# 05_RS232_USB.net
KiCad netlist of a schematic drawn in Altium Designer
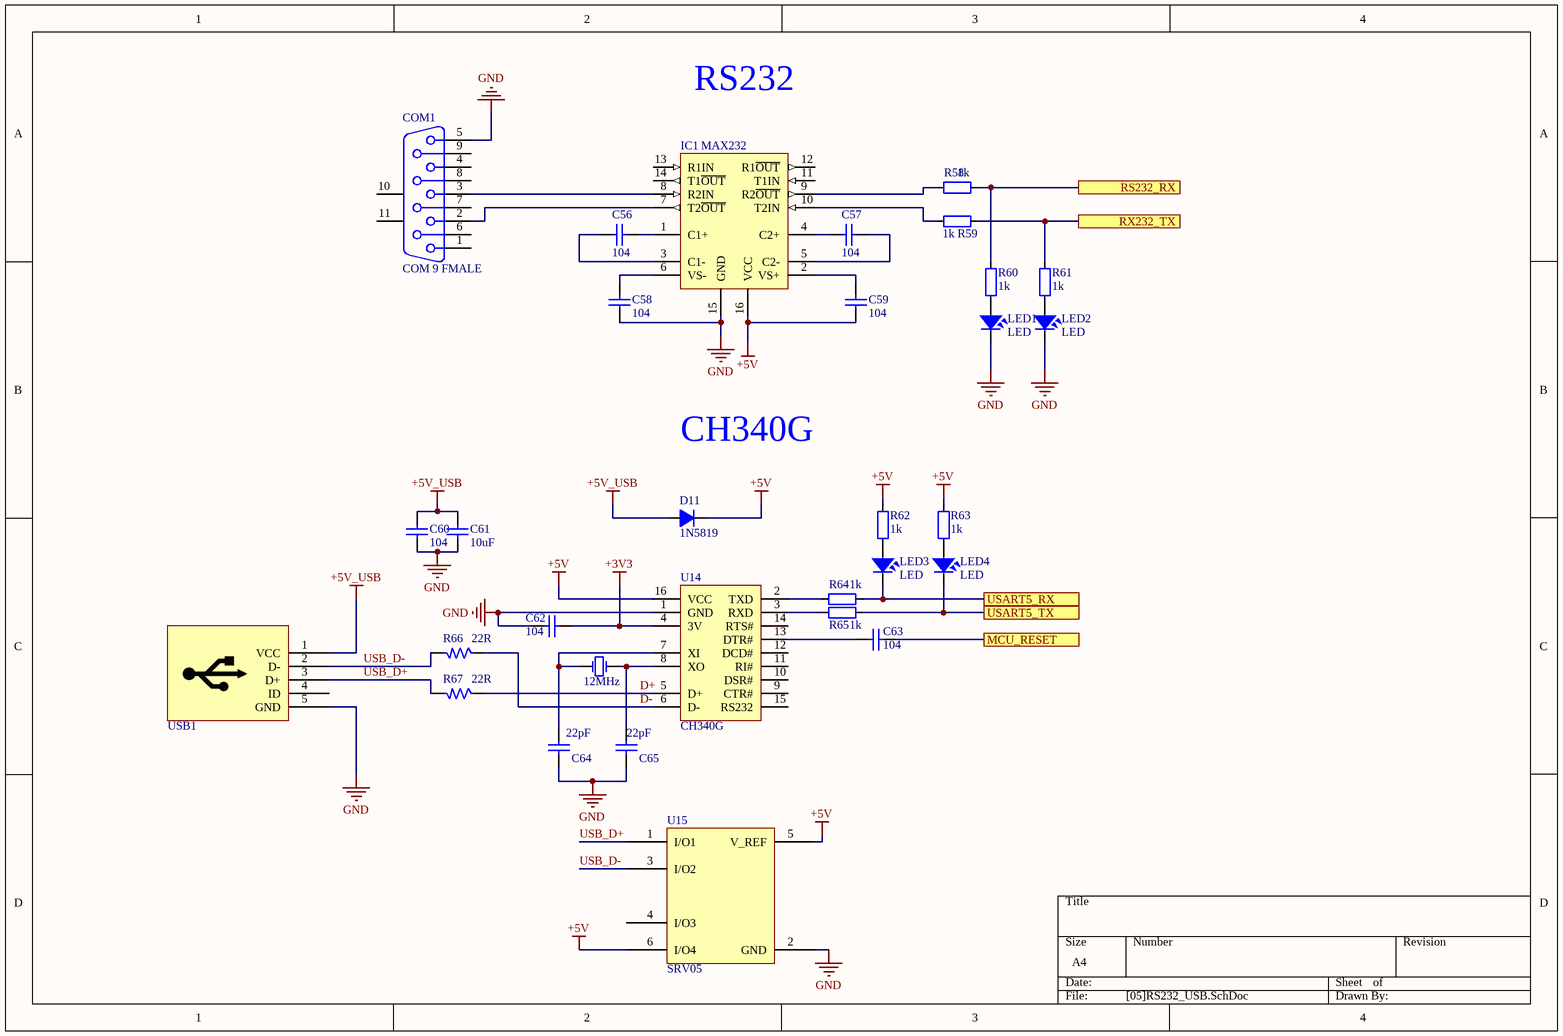
[diagram p0: [05]RS232_USB.SchDoc]

(export (version "E")
  (design (tool "Eeschema 10.0.6"))
  (components
    (comp (ref "C56")
      (value "104")
      (footprint "CAP_0603")
      (description "Capacitor")
      (fields (field (name "PUBLISHER") "Altium Limited"))
      (libsource (lib "My Library") (part "CapSMD"))
    )
    (comp (ref "C57")
      (value "104")
      (footprint "CAP_0603")
      (description "Capacitor")
      (fields (field (name "PUBLISHER") "Altium Limited"))
      (libsource (lib "My Library") (part "CapSMD"))
    )
    (comp (ref "C58")
      (value "104")
      (footprint "CAP_0603")
      (description "Capacitor")
      (fields (field (name "PUBLISHER") "Altium Limited"))
      (libsource (lib "My Library") (part "CapSMD"))
    )
    (comp (ref "C59")
      (value "104")
      (footprint "CAP_0603")
      (description "Capacitor")
      (fields (field (name "PUBLISHER") "Altium Limited"))
      (libsource (lib "My Library") (part "CapSMD"))
    )
    (comp (ref "C60")
      (value "104")
      (footprint "CAP_0603")
      (description "Capacitor")
      (fields (field (name "PUBLISHER") "Altium Limited"))
      (libsource (lib "My Library") (part "CapSMD"))
    )
    (comp (ref "C61")
      (value "10uF")
      (footprint "CAP_0603")
      (description "Capacitor")
      (fields (field (name "PUBLISHER") "Altium Limited"))
      (libsource (lib "My Library") (part "CapSMD"))
    )
    (comp (ref "C62")
      (value "104")
      (footprint "CAP_0603")
      (description "Capacitor")
      (fields (field (name "PUBLISHER") "Altium Limited"))
      (libsource (lib "My Library") (part "CapSMD"))
    )
    (comp (ref "C63")
      (value "104")
      (footprint "CAP_0603")
      (description "Capacitor")
      (fields (field (name "PUBLISHER") "Altium Limited"))
      (libsource (lib "My Library") (part "CapSMD"))
    )
    (comp (ref "C64")
      (value "22pF")
      (footprint "CAP_0603")
      (description "Capacitor")
      (fields (field (name "PUBLISHER") "Altium Limited"))
      (libsource (lib "My Library") (part "CapSMD"))
    )
    (comp (ref "C65")
      (value "22pF")
      (footprint "CAP_0603")
      (description "Capacitor")
      (fields (field (name "PUBLISHER") "Altium Limited"))
      (libsource (lib "My Library") (part "CapSMD"))
    )
    (comp (ref "COM1")
      (value "COM 9 FMALE")
      (footprint "DSB 9-F")
      (description "COM 9")
      (fields (field (name "PUBLISHER") "Altium Limited"))
      (libsource (lib "syhaunguyen") (part "DSB9F"))
    )
    (comp (ref "D11")
      (value "1N5819")
      (footprint "DO-214AB SMA")
      (description "Diode 1A")
      (libsource (lib "GPS_Traking_V1_1") (part "D1A_1"))
    )
    (comp (ref "IC1")
      (value "MAX232")
      (footprint "MAX232DR")
      (description "Dual EIA-232 Driver/Receiver")
      (libsource (lib "My Library") (part "MAX232"))
    )
    (comp (ref "LED1")
      (value "LED")
      (footprint "LED-0805-Green")
      (description "LED Single colour Green and Red")
      (libsource (lib "My Library") (part "LED"))
    )
    (comp (ref "LED2")
      (value "LED")
      (footprint "LED-0805-Green")
      (description "LED Single colour Green and Red")
      (libsource (lib "My Library") (part "LED"))
    )
    (comp (ref "LED3")
      (value "LED")
      (footprint "LED-0805-Green")
      (description "LED Single colour Green and Red")
      (libsource (lib "My Library") (part "LED"))
    )
    (comp (ref "LED4")
      (value "LED")
      (footprint "LED-0805-Green")
      (description "LED Single colour Green and Red")
      (libsource (lib "My Library") (part "LED"))
    )
    (comp (ref "R58")
      (value "1k")
      (footprint "RES-SMD-0603")
      (description "Resistor")
      (fields
        (field (name "MANUFACTURER") "Generic Components")
        (field (name "PUBLISHER") "Altium Hobart Technology Centre")
      )
      (libsource (lib "My Library") (part "Resistor - SMD"))
    )
    (comp (ref "R59")
      (value "1k")
      (footprint "RES-SMD-0603")
      (description "Resistor")
      (fields
        (field (name "MANUFACTURER") "Generic Components")
        (field (name "PUBLISHER") "Altium Hobart Technology Centre")
      )
      (libsource (lib "My Library") (part "Resistor - SMD"))
    )
    (comp (ref "R60")
      (value "1k")
      (footprint "RES-SMD-0603")
      (description "Resistor")
      (fields
        (field (name "MANUFACTURER") "Generic Components")
        (field (name "PUBLISHER") "Altium Hobart Technology Centre")
      )
      (libsource (lib "My Library") (part "Resistor - SMD"))
    )
    (comp (ref "R61")
      (value "1k")
      (footprint "RES-SMD-0603")
      (description "Resistor")
      (fields
        (field (name "MANUFACTURER") "Generic Components")
        (field (name "PUBLISHER") "Altium Hobart Technology Centre")
      )
      (libsource (lib "My Library") (part "Resistor - SMD"))
    )
    (comp (ref "R62")
      (value "1k")
      (footprint "RES-SMD-0603")
      (description "Resistor")
      (fields
        (field (name "MANUFACTURER") "Generic Components")
        (field (name "PUBLISHER") "Altium Hobart Technology Centre")
      )
      (libsource (lib "My Library") (part "Resistor - SMD"))
    )
    (comp (ref "R63")
      (value "1k")
      (footprint "RES-SMD-0603")
      (description "Resistor")
      (fields
        (field (name "MANUFACTURER") "Generic Components")
        (field (name "PUBLISHER") "Altium Hobart Technology Centre")
      )
      (libsource (lib "My Library") (part "Resistor - SMD"))
    )
    (comp (ref "R64")
      (value "1k")
      (footprint "RES-SMD-0603")
      (description "Resistor")
      (fields
        (field (name "MANUFACTURER") "Generic Components")
        (field (name "PUBLISHER") "Altium Hobart Technology Centre")
      )
      (libsource (lib "My Library") (part "Resistor - SMD"))
    )
    (comp (ref "R65")
      (value "1k")
      (footprint "RES-SMD-0603")
      (description "Resistor")
      (fields
        (field (name "MANUFACTURER") "Generic Components")
        (field (name "PUBLISHER") "Altium Hobart Technology Centre")
      )
      (libsource (lib "My Library") (part "Resistor - SMD"))
    )
    (comp (ref "R66")
      (value "22R")
      (footprint "RES-SMD-0603")
      (description "Resistor SMD")
      (libsource (lib "GPS_Traking_V1_1") (part "RM"))
    )
    (comp (ref "R67")
      (value "22R")
      (footprint "RES-SMD-0603")
      (description "Resistor SMD")
      (libsource (lib "GPS_Traking_V1_1") (part "RM"))
    )
    (comp (ref "U14")
      (value "CH340G")
      (footprint "SO16")
      (description "High and Low Side Driver")
      (fields (field (name "PUBLISHER") "Altium Limited"))
      (libsource (lib "My Library") (part "CH340G"))
    )
    (comp (ref "U15")
      (value "SRV05")
      (footprint "SOT23-6")
      (description "TVS DIODE 5V")
      (libsource (lib "My Library") (part "SRV05"))
    )
    (comp (ref "USB1") (value "USB") (footprint "USB-B-Mini") (libsource (lib "My Library") (part "USB-M")))
    (comp (ref "Y2")
      (value "12MHz")
      (footprint "XTAL-5032")
      (description "Crystal Oscillator")
      (fields (field (name "PUBLISHER") "Altium Limited"))
      (libsource (lib "My Library") (part "XTAL"))
    )
  )
  (nets
    (net (code "1") (name "+3V3") (class "Default")
      (node (ref "C62") (pin "2") (pinfunction "2_2") (pintype "passive"))
      (node (ref "U14") (pin "4") (pinfunction "3V_4") (pintype "passive"))
    )
    (net (code "2") (name "+5V") (class "Default")
      (node (ref "C59") (pin "2") (pinfunction "2_2") (pintype "passive"))
      (node (ref "D11") (pin "2") (pinfunction "K_2") (pintype "passive"))
      (node (ref "IC1") (pin "16") (pinfunction "VCC_16") (pintype "power_in"))
      (node (ref "R62") (pin "2") (pinfunction "2_2") (pintype "passive"))
      (node (ref "R63") (pin "2") (pinfunction "2_2") (pintype "passive"))
      (node (ref "U14") (pin "16") (pinfunction "VCC_16") (pintype "passive"))
      (node (ref "U15") (pin "5") (pinfunction "V_REF_5") (pintype "passive"))
      (node (ref "U15") (pin "6") (pinfunction "I/O4_6") (pintype "passive"))
    )
    (net (code "3") (name "+5V_USB") (class "Default")
      (node (ref "C60") (pin "2") (pinfunction "2_2") (pintype "passive"))
      (node (ref "C61") (pin "2") (pinfunction "2_2") (pintype "passive"))
      (node (ref "D11") (pin "1") (pinfunction "A_1") (pintype "passive"))
      (node (ref "USB1") (pin "1") (pinfunction "VCC_1") (pintype "passive"))
    )
    (net (code "4") (name "/D+") (class "Default")
      (node (ref "R67") (pin "1") (pinfunction "1_1") (pintype "passive"))
      (node (ref "U14") (pin "5") (pinfunction "D+_5") (pintype "passive"))
    )
    (net (code "5") (name "/D-") (class "Default")
      (node (ref "R66") (pin "1") (pinfunction "1_1") (pintype "passive"))
      (node (ref "U14") (pin "6") (pinfunction "D-_6") (pintype "passive"))
    )
    (net (code "6") (name "/MCU_RESET") (class "Default")
      (node (ref "C63") (pin "2") (pinfunction "2_2") (pintype "passive"))
    )
    (net (code "7") (name "/RS232_RX") (class "Default")
      (node (ref "R58") (pin "1") (pinfunction "1_1") (pintype "passive"))
      (node (ref "R60") (pin "2") (pinfunction "2_2") (pintype "passive"))
    )
    (net (code "8") (name "/RX232_TX") (class "Default")
      (node (ref "R59") (pin "1") (pinfunction "1_1") (pintype "passive"))
      (node (ref "R61") (pin "2") (pinfunction "2_2") (pintype "passive"))
    )
    (net (code "9") (name "/USART5_RX") (class "Default")
      (node (ref "LED3") (pin "2") (pinfunction "2_2") (pintype "passive"))
      (node (ref "R64") (pin "2") (pinfunction "2_2") (pintype "passive"))
    )
    (net (code "10") (name "/USART5_TX") (class "Default")
      (node (ref "LED4") (pin "2") (pinfunction "2_2") (pintype "passive"))
      (node (ref "R65") (pin "2") (pinfunction "2_2") (pintype "passive"))
    )
    (net (code "11") (name "/USB_D+") (class "Default")
      (node (ref "R67") (pin "2") (pinfunction "2_2") (pintype "passive"))
      (node (ref "U15") (pin "1") (pinfunction "I/O1_1") (pintype "passive"))
      (node (ref "USB1") (pin "3") (pinfunction "D+_3") (pintype "passive"))
    )
    (net (code "12") (name "/USB_D-") (class "Default")
      (node (ref "R66") (pin "2") (pinfunction "2_2") (pintype "passive"))
      (node (ref "U15") (pin "3") (pinfunction "I/O2_3") (pintype "passive"))
      (node (ref "USB1") (pin "2") (pinfunction "D-_2") (pintype "passive"))
    )
    (net (code "13") (name "GND") (class "Default")
      (node (ref "C58") (pin "2") (pinfunction "2_2") (pintype "passive"))
      (node (ref "C60") (pin "1") (pinfunction "1_1") (pintype "passive"))
      (node (ref "C61") (pin "1") (pinfunction "1_1") (pintype "passive"))
      (node (ref "C62") (pin "1") (pinfunction "1_1") (pintype "passive"))
      (node (ref "C64") (pin "2") (pinfunction "2_2") (pintype "passive"))
      (node (ref "C65") (pin "2") (pinfunction "2_2") (pintype "passive"))
      (node (ref "COM1") (pin "5") (pinfunction "5_5") (pintype "passive"))
      (node (ref "IC1") (pin "15") (pinfunction "GND_15") (pintype "power_in"))
      (node (ref "LED1") (pin "2") (pinfunction "2_2") (pintype "passive"))
      (node (ref "LED2") (pin "2") (pinfunction "2_2") (pintype "passive"))
      (node (ref "U14") (pin "1") (pinfunction "GND_1") (pintype "passive"))
      (node (ref "U15") (pin "2") (pinfunction "GND_2") (pintype "passive"))
      (node (ref "USB1") (pin "5") (pinfunction "GND_5") (pintype "passive"))
    )
    (net (code "14") (name "Net-(IC1-C1+)") (class "Default")
      (node (ref "C56") (pin "1") (pinfunction "1_1") (pintype "passive"))
      (node (ref "IC1") (pin "1") (pinfunction "C1+_1") (pintype "passive"))
    )
    (net (code "15") (name "Net-(IC1-C1-)") (class "Default")
      (node (ref "C56") (pin "2") (pinfunction "2_2") (pintype "passive"))
      (node (ref "IC1") (pin "3") (pinfunction "C1-_3") (pintype "passive"))
    )
    (net (code "16") (name "Net-(IC1-C2+)") (class "Default")
      (node (ref "C57") (pin "2") (pinfunction "2_2") (pintype "passive"))
      (node (ref "IC1") (pin "4") (pinfunction "C2+_4") (pintype "passive"))
    )
    (net (code "17") (name "Net-(IC1-C2-)") (class "Default")
      (node (ref "C57") (pin "1") (pinfunction "1_1") (pintype "passive"))
      (node (ref "IC1") (pin "5") (pinfunction "C2-_5") (pintype "passive"))
    )
    (net (code "18") (name "Net-(IC1-R2IN)") (class "Default")
      (node (ref "COM1") (pin "3") (pinfunction "3_3") (pintype "passive"))
      (node (ref "IC1") (pin "8") (pinfunction "R2IN_8") (pintype "input"))
    )
    (net (code "19") (name "Net-(IC1-R2~{OUT})") (class "Default")
      (node (ref "IC1") (pin "9") (pinfunction "R2~{OUT}_9") (pintype "output"))
      (node (ref "R58") (pin "2") (pinfunction "2_2") (pintype "passive"))
    )
    (net (code "20") (name "Net-(IC1-T2IN)") (class "Default")
      (node (ref "IC1") (pin "10") (pinfunction "T2IN_10") (pintype "input"))
      (node (ref "R59") (pin "2") (pinfunction "2_2") (pintype "passive"))
    )
    (net (code "21") (name "Net-(IC1-T2~{OUT})") (class "Default")
      (node (ref "COM1") (pin "2") (pinfunction "2_2") (pintype "passive"))
      (node (ref "IC1") (pin "7") (pinfunction "T2~{OUT}_7") (pintype "output"))
    )
    (net (code "22") (name "Net-(IC1-VS+)") (class "Default")
      (node (ref "C59") (pin "1") (pinfunction "1_1") (pintype "passive"))
      (node (ref "IC1") (pin "2") (pinfunction "VS+_2") (pintype "power_in"))
    )
    (net (code "23") (name "Net-(IC1-VS-)") (class "Default")
      (node (ref "C58") (pin "1") (pinfunction "1_1") (pintype "passive"))
      (node (ref "IC1") (pin "6") (pinfunction "VS-_6") (pintype "power_in"))
    )
    (net (code "24") (name "Net-(LED1-Pad1)") (class "Default")
      (node (ref "LED1") (pin "1") (pinfunction "1_1") (pintype "passive"))
      (node (ref "R60") (pin "1") (pinfunction "1_1") (pintype "passive"))
    )
    (net (code "25") (name "Net-(LED2-Pad1)") (class "Default")
      (node (ref "LED2") (pin "1") (pinfunction "1_1") (pintype "passive"))
      (node (ref "R61") (pin "1") (pinfunction "1_1") (pintype "passive"))
    )
    (net (code "26") (name "Net-(LED3-Pad1)") (class "Default")
      (node (ref "LED3") (pin "1") (pinfunction "1_1") (pintype "passive"))
      (node (ref "R62") (pin "1") (pinfunction "1_1") (pintype "passive"))
    )
    (net (code "27") (name "Net-(LED4-Pad1)") (class "Default")
      (node (ref "LED4") (pin "1") (pinfunction "1_1") (pintype "passive"))
      (node (ref "R63") (pin "1") (pinfunction "1_1") (pintype "passive"))
    )
    (net (code "28") (name "Net-(U14-DTR#)") (class "Default")
      (node (ref "C63") (pin "1") (pinfunction "1_1") (pintype "passive"))
      (node (ref "U14") (pin "13") (pinfunction "DTR#_13") (pintype "passive"))
    )
    (net (code "29") (name "Net-(U14-RXD)") (class "Default")
      (node (ref "R65") (pin "1") (pinfunction "1_1") (pintype "passive"))
      (node (ref "U14") (pin "3") (pinfunction "RXD_3") (pintype "passive"))
    )
    (net (code "30") (name "Net-(U14-TXD)") (class "Default")
      (node (ref "R64") (pin "1") (pinfunction "1_1") (pintype "passive"))
      (node (ref "U14") (pin "2") (pinfunction "TXD_2") (pintype "passive"))
    )
    (net (code "31") (name "Net-(U14-XI)") (class "Default")
      (node (ref "C64") (pin "1") (pinfunction "1_1") (pintype "passive"))
      (node (ref "U14") (pin "7") (pinfunction "XI_7") (pintype "passive"))
      (node (ref "Y2") (pin "1") (pinfunction "OSC1_1") (pintype "passive"))
    )
    (net (code "32") (name "Net-(U14-XO)") (class "Default")
      (node (ref "C65") (pin "1") (pinfunction "1_1") (pintype "passive"))
      (node (ref "U14") (pin "8") (pinfunction "XO_8") (pintype "passive"))
      (node (ref "Y2") (pin "2") (pinfunction "OSC2_2") (pintype "passive"))
    )
    (net (code "33") (name "unconnected-(COM1-MH1-Pad10)") (class "Default")
      (node (ref "COM1") (pin "10") (pinfunction "MH1_10") (pintype "passive"))
    )
    (net (code "34") (name "unconnected-(COM1-MH2-Pad11)") (class "Default")
      (node (ref "COM1") (pin "11") (pinfunction "MH2_11") (pintype "passive"))
    )
    (net (code "35") (name "unconnected-(COM1-Pad1)") (class "Default")
      (node (ref "COM1") (pin "1") (pinfunction "1_1") (pintype "passive"))
    )
    (net (code "36") (name "unconnected-(COM1-Pad4)") (class "Default")
      (node (ref "COM1") (pin "4") (pinfunction "4_4") (pintype "passive"))
    )
    (net (code "37") (name "unconnected-(COM1-Pad6)") (class "Default")
      (node (ref "COM1") (pin "6") (pinfunction "6_6") (pintype "passive"))
    )
    (net (code "38") (name "unconnected-(COM1-Pad7)") (class "Default")
      (node (ref "COM1") (pin "7") (pinfunction "7_7") (pintype "passive"))
    )
    (net (code "39") (name "unconnected-(COM1-Pad8)") (class "Default")
      (node (ref "COM1") (pin "8") (pinfunction "8_8") (pintype "passive"))
    )
    (net (code "40") (name "unconnected-(COM1-Pad9)") (class "Default")
      (node (ref "COM1") (pin "9") (pinfunction "9_9") (pintype "passive"))
    )
    (net (code "41") (name "unconnected-(IC1-R1IN-Pad13)") (class "Default")
      (node (ref "IC1") (pin "13") (pinfunction "R1IN_13") (pintype "input"))
    )
    (net (code "42") (name "unconnected-(IC1-R1~{OUT}-Pad12)") (class "Default")
      (node (ref "IC1") (pin "12") (pinfunction "R1~{OUT}_12") (pintype "output"))
    )
    (net (code "43") (name "unconnected-(IC1-T1IN-Pad11)") (class "Default")
      (node (ref "IC1") (pin "11") (pinfunction "T1IN_11") (pintype "input"))
    )
    (net (code "44") (name "unconnected-(IC1-T1~{OUT}-Pad14)") (class "Default")
      (node (ref "IC1") (pin "14") (pinfunction "T1~{OUT}_14") (pintype "output"))
    )
    (net (code "45") (name "unconnected-(U14-CTR#-Pad9)") (class "Default")
      (node (ref "U14") (pin "9") (pinfunction "CTR#_9") (pintype "passive"))
    )
    (net (code "46") (name "unconnected-(U14-DCD#-Pad12)") (class "Default")
      (node (ref "U14") (pin "12") (pinfunction "DCD#_12") (pintype "passive"))
    )
    (net (code "47") (name "unconnected-(U14-DSR#-Pad10)") (class "Default")
      (node (ref "U14") (pin "10") (pinfunction "DSR#_10") (pintype "passive"))
    )
    (net (code "48") (name "unconnected-(U14-RI#-Pad11)") (class "Default")
      (node (ref "U14") (pin "11") (pinfunction "RI#_11") (pintype "passive"))
    )
    (net (code "49") (name "unconnected-(U14-RS232-Pad15)") (class "Default")
      (node (ref "U14") (pin "15") (pinfunction "RS232_15") (pintype "passive"))
    )
    (net (code "50") (name "unconnected-(U14-RTS#-Pad14)") (class "Default")
      (node (ref "U14") (pin "14") (pinfunction "RTS#_14") (pintype "passive"))
    )
    (net (code "51") (name "unconnected-(U15-I{slash}O3-Pad4)") (class "Default")
      (node (ref "U15") (pin "4") (pinfunction "I/O3_4") (pintype "passive"))
    )
    (net (code "52") (name "unconnected-(USB1-ID-Pad4)") (class "Default")
      (node (ref "USB1") (pin "4") (pinfunction "ID_4") (pintype "passive"))
    )
  )
)
